# Connectors.net
KiCad netlist of a schematic drawn in Altium Designer
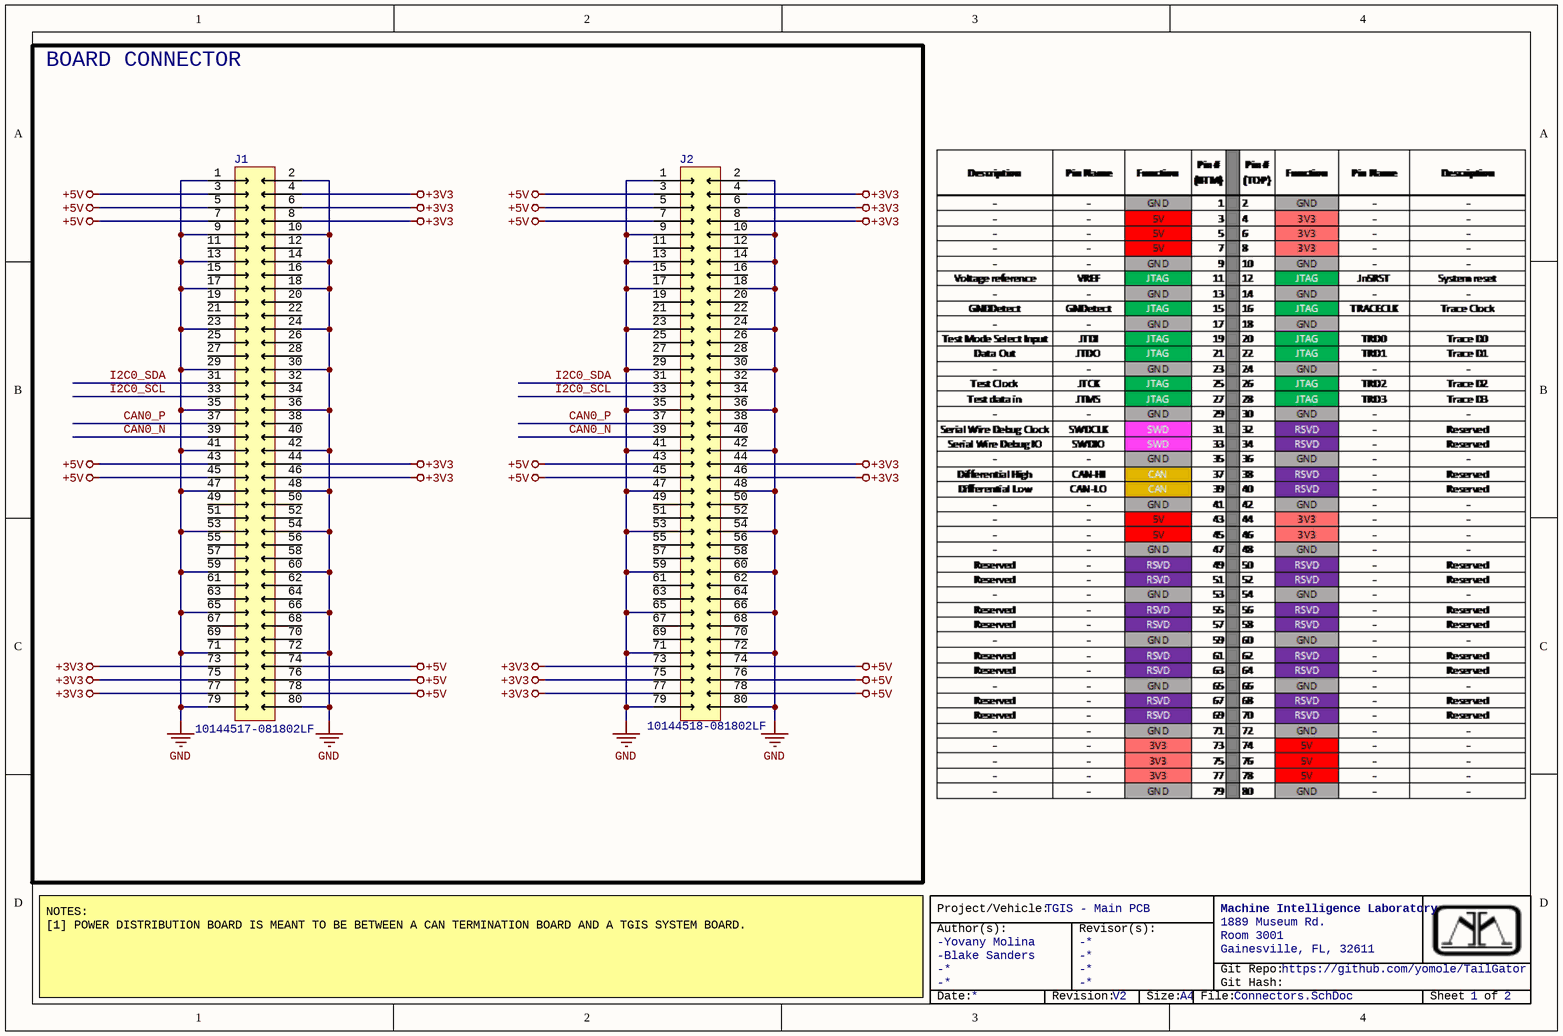
[diagram p0: Connectors.SchDoc]

(export (version "E")
  (design (tool "Eeschema 10.0.6"))
  (components
    (comp (ref "J1")
      (value "10144517-081802LF")
      (footprint "AMPHENOL_10144517-081802LF")
      (description "CONN RCPT 1 80POS SMD GOLD")
      (libsource (lib "TGIS") (part "10144517-081802LF"))
    )
    (comp (ref "J2")
      (value "10144518-081802LF")
      (footprint "AMPHENOL_10144518-081802LF")
      (description "CONN PLUG 1 80POS SMD GOLD")
      (libsource (lib "TGIS_Connectors") (part "10144518-081802LF"))
    )
  )
  (nets
    (net (code "1") (name "+3V3") (class "Default")
      (node (ref "J1") (pin "4") (pinfunction "4_4") (pintype "passive"))
      (node (ref "J1") (pin "44") (pinfunction "44_44") (pintype "passive"))
      (node (ref "J1") (pin "46") (pinfunction "46_46") (pintype "passive"))
      (node (ref "J1") (pin "6") (pinfunction "6_6") (pintype "passive"))
      (node (ref "J1") (pin "73") (pinfunction "73_73") (pintype "passive"))
      (node (ref "J1") (pin "75") (pinfunction "75_75") (pintype "passive"))
      (node (ref "J1") (pin "77") (pinfunction "77_77") (pintype "passive"))
      (node (ref "J1") (pin "8") (pinfunction "8_8") (pintype "passive"))
      (node (ref "J2") (pin "4") (pinfunction "4_4") (pintype "passive"))
      (node (ref "J2") (pin "44") (pinfunction "44_44") (pintype "passive"))
      (node (ref "J2") (pin "46") (pinfunction "46_46") (pintype "passive"))
      (node (ref "J2") (pin "6") (pinfunction "6_6") (pintype "passive"))
      (node (ref "J2") (pin "73") (pinfunction "73_73") (pintype "passive"))
      (node (ref "J2") (pin "75") (pinfunction "75_75") (pintype "passive"))
      (node (ref "J2") (pin "77") (pinfunction "77_77") (pintype "passive"))
      (node (ref "J2") (pin "8") (pinfunction "8_8") (pintype "passive"))
    )
    (net (code "2") (name "+5V") (class "Default")
      (node (ref "J1") (pin "3") (pinfunction "3_3") (pintype "passive"))
      (node (ref "J1") (pin "43") (pinfunction "43_43") (pintype "passive"))
      (node (ref "J1") (pin "45") (pinfunction "45_45") (pintype "passive"))
      (node (ref "J1") (pin "5") (pinfunction "5_5") (pintype "passive"))
      (node (ref "J1") (pin "7") (pinfunction "7_7") (pintype "passive"))
      (node (ref "J1") (pin "74") (pinfunction "74_74") (pintype "passive"))
      (node (ref "J1") (pin "76") (pinfunction "76_76") (pintype "passive"))
      (node (ref "J1") (pin "78") (pinfunction "78_78") (pintype "passive"))
      (node (ref "J2") (pin "3") (pinfunction "3_3") (pintype "passive"))
      (node (ref "J2") (pin "43") (pinfunction "43_43") (pintype "passive"))
      (node (ref "J2") (pin "45") (pinfunction "45_45") (pintype "passive"))
      (node (ref "J2") (pin "5") (pinfunction "5_5") (pintype "passive"))
      (node (ref "J2") (pin "7") (pinfunction "7_7") (pintype "passive"))
      (node (ref "J2") (pin "74") (pinfunction "74_74") (pintype "passive"))
      (node (ref "J2") (pin "76") (pinfunction "76_76") (pintype "passive"))
      (node (ref "J2") (pin "78") (pinfunction "78_78") (pintype "passive"))
    )
    (net (code "3") (name "/CAN0_N") (class "Default")
      (node (ref "J1") (pin "39") (pinfunction "39_39") (pintype "passive"))
      (node (ref "J2") (pin "39") (pinfunction "39_39") (pintype "passive"))
    )
    (net (code "4") (name "/CAN0_P") (class "Default")
      (node (ref "J1") (pin "37") (pinfunction "37_37") (pintype "passive"))
      (node (ref "J2") (pin "37") (pinfunction "37_37") (pintype "passive"))
    )
    (net (code "5") (name "/I2C0_SCL") (class "Default")
      (node (ref "J1") (pin "33") (pinfunction "33_33") (pintype "passive"))
      (node (ref "J2") (pin "33") (pinfunction "33_33") (pintype "passive"))
    )
    (net (code "6") (name "/I2C0_SDA") (class "Default")
      (node (ref "J1") (pin "31") (pinfunction "31_31") (pintype "passive"))
      (node (ref "J2") (pin "31") (pinfunction "31_31") (pintype "passive"))
    )
    (net (code "7") (name "GND") (class "Default")
      (node (ref "J1") (pin "1") (pinfunction "1_1") (pintype "passive"))
      (node (ref "J1") (pin "10") (pinfunction "10_10") (pintype "passive"))
      (node (ref "J1") (pin "13") (pinfunction "13_13") (pintype "passive"))
      (node (ref "J1") (pin "14") (pinfunction "14_14") (pintype "passive"))
      (node (ref "J1") (pin "17") (pinfunction "17_17") (pintype "passive"))
      (node (ref "J1") (pin "18") (pinfunction "18_18") (pintype "passive"))
      (node (ref "J1") (pin "2") (pinfunction "2_2") (pintype "passive"))
      (node (ref "J1") (pin "23") (pinfunction "23_23") (pintype "passive"))
      (node (ref "J1") (pin "24") (pinfunction "24_24") (pintype "passive"))
      (node (ref "J1") (pin "29") (pinfunction "29_29") (pintype "passive"))
      (node (ref "J1") (pin "30") (pinfunction "30_30") (pintype "passive"))
      (node (ref "J1") (pin "35") (pinfunction "35_35") (pintype "passive"))
      (node (ref "J1") (pin "36") (pinfunction "36_36") (pintype "passive"))
      (node (ref "J1") (pin "41") (pinfunction "41_41") (pintype "passive"))
      (node (ref "J1") (pin "42") (pinfunction "42_42") (pintype "passive"))
      (node (ref "J1") (pin "47") (pinfunction "47_47") (pintype "passive"))
      (node (ref "J1") (pin "48") (pinfunction "48_48") (pintype "passive"))
      (node (ref "J1") (pin "53") (pinfunction "53_53") (pintype "passive"))
      (node (ref "J1") (pin "54") (pinfunction "54_54") (pintype "passive"))
      (node (ref "J1") (pin "59") (pinfunction "59_59") (pintype "passive"))
      (node (ref "J1") (pin "60") (pinfunction "60_60") (pintype "passive"))
      (node (ref "J1") (pin "65") (pinfunction "65_65") (pintype "passive"))
      (node (ref "J1") (pin "66") (pinfunction "66_66") (pintype "passive"))
      (node (ref "J1") (pin "71") (pinfunction "71_71") (pintype "passive"))
      (node (ref "J1") (pin "72") (pinfunction "72_72") (pintype "passive"))
      (node (ref "J1") (pin "79") (pinfunction "79_79") (pintype "passive"))
      (node (ref "J1") (pin "80") (pinfunction "80_80") (pintype "passive"))
      (node (ref "J1") (pin "9") (pinfunction "9_9") (pintype "passive"))
      (node (ref "J2") (pin "1") (pinfunction "1_1") (pintype "passive"))
      (node (ref "J2") (pin "10") (pinfunction "10_10") (pintype "passive"))
      (node (ref "J2") (pin "13") (pinfunction "13_13") (pintype "passive"))
      (node (ref "J2") (pin "14") (pinfunction "14_14") (pintype "passive"))
      (node (ref "J2") (pin "17") (pinfunction "17_17") (pintype "passive"))
      (node (ref "J2") (pin "18") (pinfunction "18_18") (pintype "passive"))
      (node (ref "J2") (pin "2") (pinfunction "2_2") (pintype "passive"))
      (node (ref "J2") (pin "23") (pinfunction "23_23") (pintype "passive"))
      (node (ref "J2") (pin "24") (pinfunction "24_24") (pintype "passive"))
      (node (ref "J2") (pin "29") (pinfunction "29_29") (pintype "passive"))
      (node (ref "J2") (pin "30") (pinfunction "30_30") (pintype "passive"))
      (node (ref "J2") (pin "35") (pinfunction "35_35") (pintype "passive"))
      (node (ref "J2") (pin "36") (pinfunction "36_36") (pintype "passive"))
      (node (ref "J2") (pin "41") (pinfunction "41_41") (pintype "passive"))
      (node (ref "J2") (pin "42") (pinfunction "42_42") (pintype "passive"))
      (node (ref "J2") (pin "47") (pinfunction "47_47") (pintype "passive"))
      (node (ref "J2") (pin "48") (pinfunction "48_48") (pintype "passive"))
      (node (ref "J2") (pin "53") (pinfunction "53_53") (pintype "passive"))
      (node (ref "J2") (pin "54") (pinfunction "54_54") (pintype "passive"))
      (node (ref "J2") (pin "59") (pinfunction "59_59") (pintype "passive"))
      (node (ref "J2") (pin "60") (pinfunction "60_60") (pintype "passive"))
      (node (ref "J2") (pin "65") (pinfunction "65_65") (pintype "passive"))
      (node (ref "J2") (pin "66") (pinfunction "66_66") (pintype "passive"))
      (node (ref "J2") (pin "71") (pinfunction "71_71") (pintype "passive"))
      (node (ref "J2") (pin "72") (pinfunction "72_72") (pintype "passive"))
      (node (ref "J2") (pin "79") (pinfunction "79_79") (pintype "passive"))
      (node (ref "J2") (pin "80") (pinfunction "80_80") (pintype "passive"))
      (node (ref "J2") (pin "9") (pinfunction "9_9") (pintype "passive"))
    )
    (net (code "8") (name "unconnected-(J1-Pad11)") (class "Default")
      (node (ref "J1") (pin "11") (pinfunction "11_11") (pintype "passive"))
    )
    (net (code "9") (name "unconnected-(J1-Pad12)") (class "Default")
      (node (ref "J1") (pin "12") (pinfunction "12_12") (pintype "passive"))
    )
    (net (code "10") (name "unconnected-(J1-Pad15)") (class "Default")
      (node (ref "J1") (pin "15") (pinfunction "15_15") (pintype "passive"))
    )
    (net (code "11") (name "unconnected-(J1-Pad16)") (class "Default")
      (node (ref "J1") (pin "16") (pinfunction "16_16") (pintype "passive"))
    )
    (net (code "12") (name "unconnected-(J1-Pad19)") (class "Default")
      (node (ref "J1") (pin "19") (pinfunction "19_19") (pintype "passive"))
    )
    (net (code "13") (name "unconnected-(J1-Pad20)") (class "Default")
      (node (ref "J1") (pin "20") (pinfunction "20_20") (pintype "passive"))
    )
    (net (code "14") (name "unconnected-(J1-Pad21)") (class "Default")
      (node (ref "J1") (pin "21") (pinfunction "21_21") (pintype "passive"))
    )
    (net (code "15") (name "unconnected-(J1-Pad22)") (class "Default")
      (node (ref "J1") (pin "22") (pinfunction "22_22") (pintype "passive"))
    )
    (net (code "16") (name "unconnected-(J1-Pad25)") (class "Default")
      (node (ref "J1") (pin "25") (pinfunction "25_25") (pintype "passive"))
    )
    (net (code "17") (name "unconnected-(J1-Pad26)") (class "Default")
      (node (ref "J1") (pin "26") (pinfunction "26_26") (pintype "passive"))
    )
    (net (code "18") (name "unconnected-(J1-Pad27)") (class "Default")
      (node (ref "J1") (pin "27") (pinfunction "27_27") (pintype "passive"))
    )
    (net (code "19") (name "unconnected-(J1-Pad28)") (class "Default")
      (node (ref "J1") (pin "28") (pinfunction "28_28") (pintype "passive"))
    )
    (net (code "20") (name "unconnected-(J1-Pad32)") (class "Default")
      (node (ref "J1") (pin "32") (pinfunction "32_32") (pintype "passive"))
    )
    (net (code "21") (name "unconnected-(J1-Pad34)") (class "Default")
      (node (ref "J1") (pin "34") (pinfunction "34_34") (pintype "passive"))
    )
    (net (code "22") (name "unconnected-(J1-Pad38)") (class "Default")
      (node (ref "J1") (pin "38") (pinfunction "38_38") (pintype "passive"))
    )
    (net (code "23") (name "unconnected-(J1-Pad40)") (class "Default")
      (node (ref "J1") (pin "40") (pinfunction "40_40") (pintype "passive"))
    )
    (net (code "24") (name "unconnected-(J1-Pad49)") (class "Default")
      (node (ref "J1") (pin "49") (pinfunction "49_49") (pintype "passive"))
    )
    (net (code "25") (name "unconnected-(J1-Pad50)") (class "Default")
      (node (ref "J1") (pin "50") (pinfunction "50_50") (pintype "passive"))
    )
    (net (code "26") (name "unconnected-(J1-Pad51)") (class "Default")
      (node (ref "J1") (pin "51") (pinfunction "51_51") (pintype "passive"))
    )
    (net (code "27") (name "unconnected-(J1-Pad52)") (class "Default")
      (node (ref "J1") (pin "52") (pinfunction "52_52") (pintype "passive"))
    )
    (net (code "28") (name "unconnected-(J1-Pad55)") (class "Default")
      (node (ref "J1") (pin "55") (pinfunction "55_55") (pintype "passive"))
    )
    (net (code "29") (name "unconnected-(J1-Pad56)") (class "Default")
      (node (ref "J1") (pin "56") (pinfunction "56_56") (pintype "passive"))
    )
    (net (code "30") (name "unconnected-(J1-Pad57)") (class "Default")
      (node (ref "J1") (pin "57") (pinfunction "57_57") (pintype "passive"))
    )
    (net (code "31") (name "unconnected-(J1-Pad58)") (class "Default")
      (node (ref "J1") (pin "58") (pinfunction "58_58") (pintype "passive"))
    )
    (net (code "32") (name "unconnected-(J1-Pad61)") (class "Default")
      (node (ref "J1") (pin "61") (pinfunction "61_61") (pintype "passive"))
    )
    (net (code "33") (name "unconnected-(J1-Pad62)") (class "Default")
      (node (ref "J1") (pin "62") (pinfunction "62_62") (pintype "passive"))
    )
    (net (code "34") (name "unconnected-(J1-Pad63)") (class "Default")
      (node (ref "J1") (pin "63") (pinfunction "63_63") (pintype "passive"))
    )
    (net (code "35") (name "unconnected-(J1-Pad64)") (class "Default")
      (node (ref "J1") (pin "64") (pinfunction "64_64") (pintype "passive"))
    )
    (net (code "36") (name "unconnected-(J1-Pad67)") (class "Default")
      (node (ref "J1") (pin "67") (pinfunction "67_67") (pintype "passive"))
    )
    (net (code "37") (name "unconnected-(J1-Pad68)") (class "Default")
      (node (ref "J1") (pin "68") (pinfunction "68_68") (pintype "passive"))
    )
    (net (code "38") (name "unconnected-(J1-Pad69)") (class "Default")
      (node (ref "J1") (pin "69") (pinfunction "69_69") (pintype "passive"))
    )
    (net (code "39") (name "unconnected-(J1-Pad70)") (class "Default")
      (node (ref "J1") (pin "70") (pinfunction "70_70") (pintype "passive"))
    )
    (net (code "40") (name "unconnected-(J2-Pad11)") (class "Default")
      (node (ref "J2") (pin "11") (pinfunction "11_11") (pintype "passive"))
    )
    (net (code "41") (name "unconnected-(J2-Pad12)") (class "Default")
      (node (ref "J2") (pin "12") (pinfunction "12_12") (pintype "passive"))
    )
    (net (code "42") (name "unconnected-(J2-Pad15)") (class "Default")
      (node (ref "J2") (pin "15") (pinfunction "15_15") (pintype "passive"))
    )
    (net (code "43") (name "unconnected-(J2-Pad16)") (class "Default")
      (node (ref "J2") (pin "16") (pinfunction "16_16") (pintype "passive"))
    )
    (net (code "44") (name "unconnected-(J2-Pad19)") (class "Default")
      (node (ref "J2") (pin "19") (pinfunction "19_19") (pintype "passive"))
    )
    (net (code "45") (name "unconnected-(J2-Pad20)") (class "Default")
      (node (ref "J2") (pin "20") (pinfunction "20_20") (pintype "passive"))
    )
    (net (code "46") (name "unconnected-(J2-Pad21)") (class "Default")
      (node (ref "J2") (pin "21") (pinfunction "21_21") (pintype "passive"))
    )
    (net (code "47") (name "unconnected-(J2-Pad22)") (class "Default")
      (node (ref "J2") (pin "22") (pinfunction "22_22") (pintype "passive"))
    )
    (net (code "48") (name "unconnected-(J2-Pad25)") (class "Default")
      (node (ref "J2") (pin "25") (pinfunction "25_25") (pintype "passive"))
    )
    (net (code "49") (name "unconnected-(J2-Pad26)") (class "Default")
      (node (ref "J2") (pin "26") (pinfunction "26_26") (pintype "passive"))
    )
    (net (code "50") (name "unconnected-(J2-Pad27)") (class "Default")
      (node (ref "J2") (pin "27") (pinfunction "27_27") (pintype "passive"))
    )
    (net (code "51") (name "unconnected-(J2-Pad28)") (class "Default")
      (node (ref "J2") (pin "28") (pinfunction "28_28") (pintype "passive"))
    )
    (net (code "52") (name "unconnected-(J2-Pad32)") (class "Default")
      (node (ref "J2") (pin "32") (pinfunction "32_32") (pintype "passive"))
    )
    (net (code "53") (name "unconnected-(J2-Pad34)") (class "Default")
      (node (ref "J2") (pin "34") (pinfunction "34_34") (pintype "passive"))
    )
    (net (code "54") (name "unconnected-(J2-Pad38)") (class "Default")
      (node (ref "J2") (pin "38") (pinfunction "38_38") (pintype "passive"))
    )
    (net (code "55") (name "unconnected-(J2-Pad40)") (class "Default")
      (node (ref "J2") (pin "40") (pinfunction "40_40") (pintype "passive"))
    )
    (net (code "56") (name "unconnected-(J2-Pad49)") (class "Default")
      (node (ref "J2") (pin "49") (pinfunction "49_49") (pintype "passive"))
    )
    (net (code "57") (name "unconnected-(J2-Pad50)") (class "Default")
      (node (ref "J2") (pin "50") (pinfunction "50_50") (pintype "passive"))
    )
    (net (code "58") (name "unconnected-(J2-Pad51)") (class "Default")
      (node (ref "J2") (pin "51") (pinfunction "51_51") (pintype "passive"))
    )
    (net (code "59") (name "unconnected-(J2-Pad52)") (class "Default")
      (node (ref "J2") (pin "52") (pinfunction "52_52") (pintype "passive"))
    )
    (net (code "60") (name "unconnected-(J2-Pad55)") (class "Default")
      (node (ref "J2") (pin "55") (pinfunction "55_55") (pintype "passive"))
    )
    (net (code "61") (name "unconnected-(J2-Pad56)") (class "Default")
      (node (ref "J2") (pin "56") (pinfunction "56_56") (pintype "passive"))
    )
    (net (code "62") (name "unconnected-(J2-Pad57)") (class "Default")
      (node (ref "J2") (pin "57") (pinfunction "57_57") (pintype "passive"))
    )
    (net (code "63") (name "unconnected-(J2-Pad58)") (class "Default")
      (node (ref "J2") (pin "58") (pinfunction "58_58") (pintype "passive"))
    )
    (net (code "64") (name "unconnected-(J2-Pad61)") (class "Default")
      (node (ref "J2") (pin "61") (pinfunction "61_61") (pintype "passive"))
    )
    (net (code "65") (name "unconnected-(J2-Pad62)") (class "Default")
      (node (ref "J2") (pin "62") (pinfunction "62_62") (pintype "passive"))
    )
    (net (code "66") (name "unconnected-(J2-Pad63)") (class "Default")
      (node (ref "J2") (pin "63") (pinfunction "63_63") (pintype "passive"))
    )
    (net (code "67") (name "unconnected-(J2-Pad64)") (class "Default")
      (node (ref "J2") (pin "64") (pinfunction "64_64") (pintype "passive"))
    )
    (net (code "68") (name "unconnected-(J2-Pad67)") (class "Default")
      (node (ref "J2") (pin "67") (pinfunction "67_67") (pintype "passive"))
    )
    (net (code "69") (name "unconnected-(J2-Pad68)") (class "Default")
      (node (ref "J2") (pin "68") (pinfunction "68_68") (pintype "passive"))
    )
    (net (code "70") (name "unconnected-(J2-Pad69)") (class "Default")
      (node (ref "J2") (pin "69") (pinfunction "69_69") (pintype "passive"))
    )
    (net (code "71") (name "unconnected-(J2-Pad70)") (class "Default")
      (node (ref "J2") (pin "70") (pinfunction "70_70") (pintype "passive"))
    )
  )
)
